# ESP-WROOM32-Breakout_v10.net
KiCad netlist of a schematic drawn in EAGLE
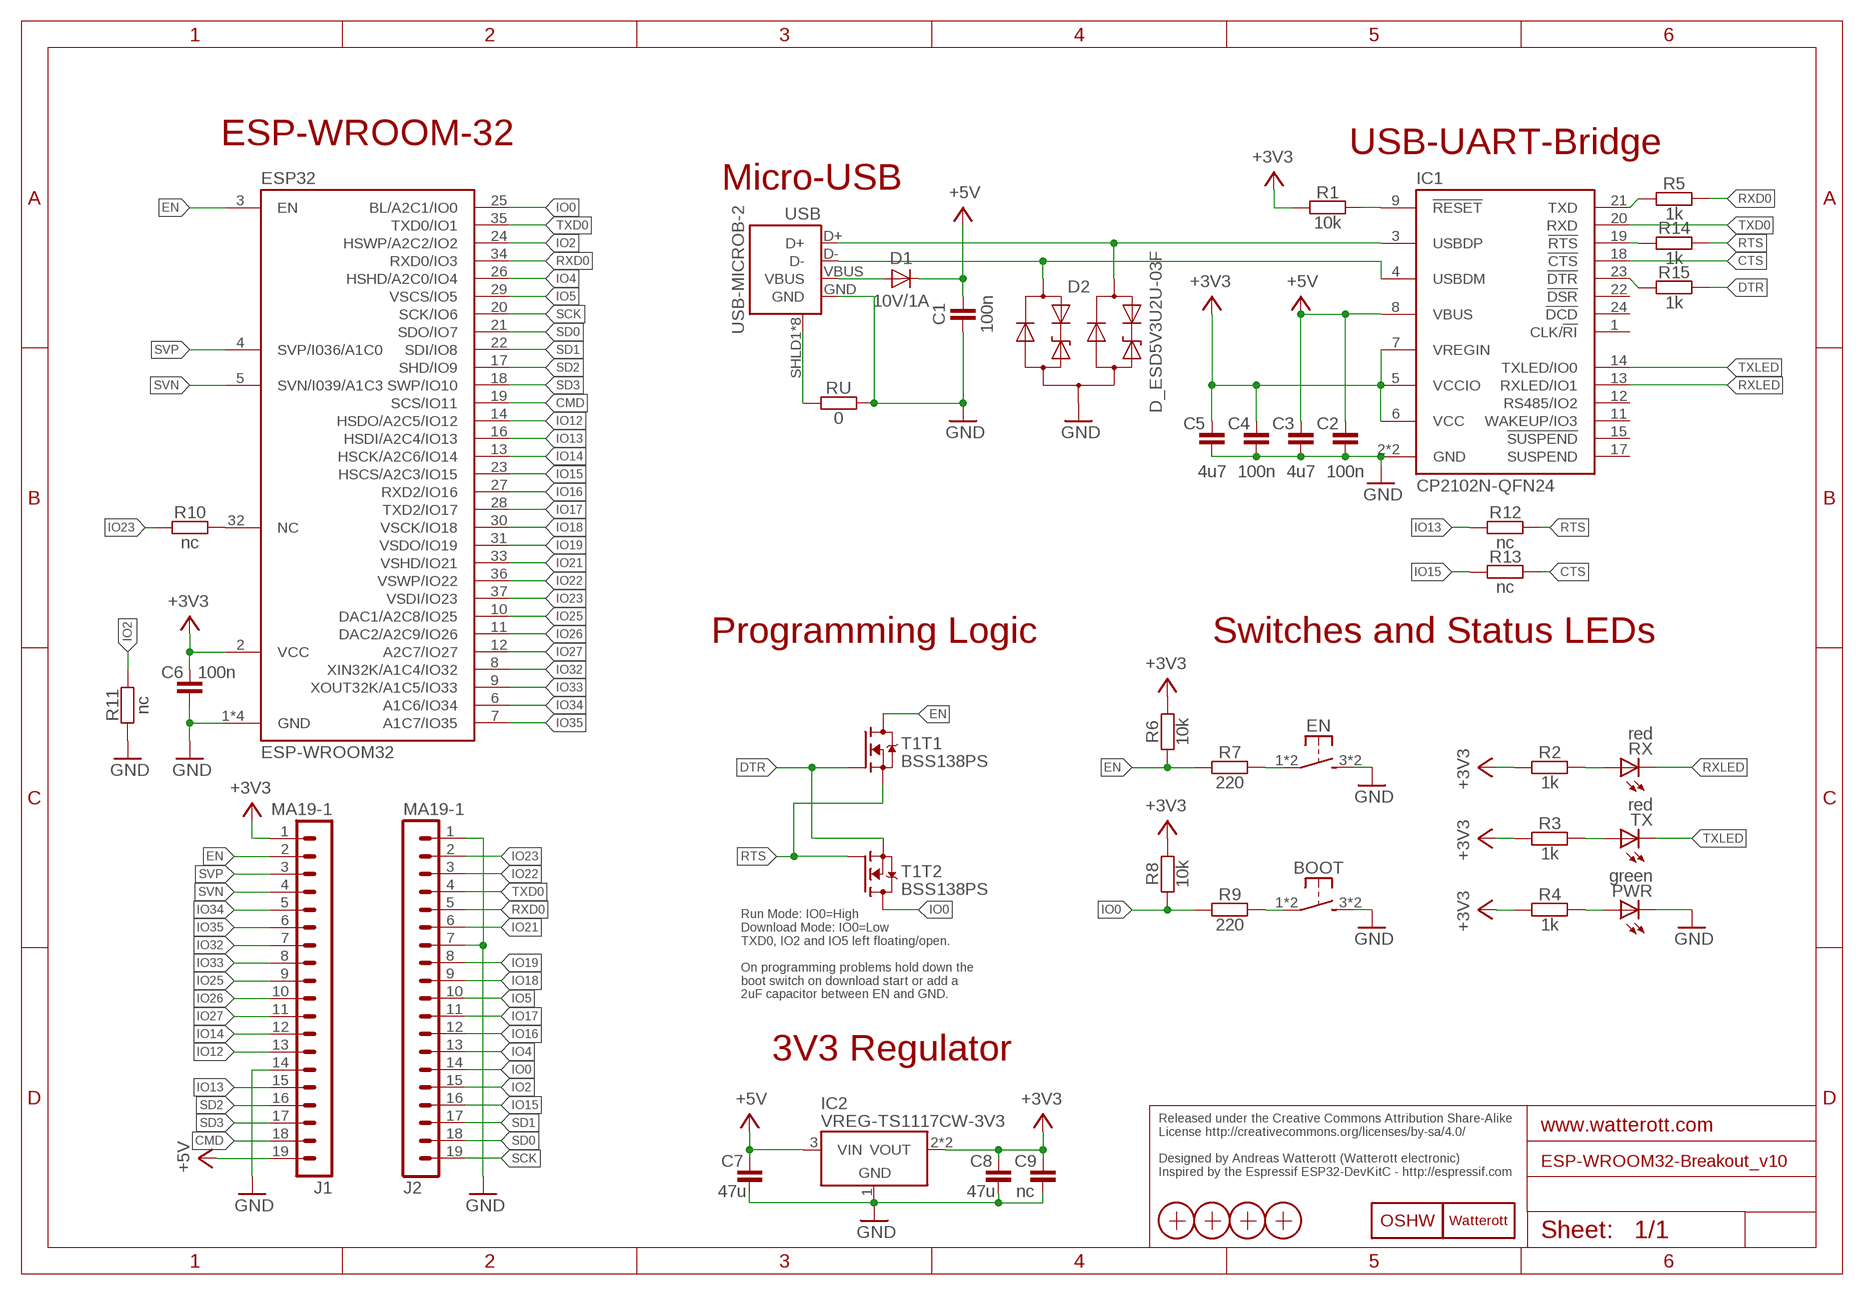
[diagram p0: schematic, sheet 1]

(export (version "E")
  (design (tool "Eeschema 10.0.6"))
  (components
    (comp (ref "BOOT")
      (value "SW-TACTILE-PTS840P")
      (footprint "eagle-import:PTS840P")
      (libsource (lib "eagle-import") (part "SW-TACTILE-PTS840P"))
    )
    (comp (ref "C1")
      (value "100n")
      (footprint "eagle-import:C0402")
      (libsource (lib "eagle-import") (part "CAPACITOR-0402"))
    )
    (comp (ref "C2")
      (value "100n")
      (footprint "eagle-import:C0402")
      (libsource (lib "eagle-import") (part "CAPACITOR-0402"))
    )
    (comp (ref "C3")
      (value "4u7")
      (footprint "eagle-import:C0603")
      (libsource (lib "eagle-import") (part "CAPACITOR-0603"))
    )
    (comp (ref "C4")
      (value "100n")
      (footprint "eagle-import:C0402")
      (libsource (lib "eagle-import") (part "CAPACITOR-0402"))
    )
    (comp (ref "C5")
      (value "4u7")
      (footprint "eagle-import:C0603")
      (libsource (lib "eagle-import") (part "CAPACITOR-0603"))
    )
    (comp (ref "C6")
      (value "100n")
      (footprint "eagle-import:C0402")
      (libsource (lib "eagle-import") (part "CAPACITOR-0402"))
    )
    (comp (ref "C7")
      (value "47u")
      (footprint "eagle-import:C1206")
      (libsource (lib "eagle-import") (part "CAPACITOR-1206"))
    )
    (comp (ref "C8")
      (value "47u")
      (footprint "eagle-import:C1206")
      (libsource (lib "eagle-import") (part "CAPACITOR-1206"))
    )
    (comp (ref "C9")
      (value "nc")
      (footprint "eagle-import:C1206")
      (libsource (lib "eagle-import") (part "CAPACITOR-1206"))
    )
    (comp (ref "D1")
      (value "10V/1A")
      (footprint "eagle-import:SMA_DO214AC")
      (libsource (lib "eagle-import") (part "DIODE-SMA"))
    )
    (comp (ref "D2")
      (value "D_ESD5V3U2U-03F")
      (footprint "eagle-import:SOT723")
      (libsource (lib "eagle-import") (part "D_ESD5V3U2U-03F"))
    )
    (comp (ref "EN")
      (value "SW-TACTILE-PTS840P")
      (footprint "eagle-import:PTS840P")
      (libsource (lib "eagle-import") (part "SW-TACTILE-PTS840P"))
    )
    (comp (ref "ESP32")
      (value "ESP-WROOM32")
      (footprint "eagle-import:ESP-WROOM32")
      (libsource (lib "eagle-import") (part "ESP-WROOM32"))
    )
    (comp (ref "IC1")
      (value "CP2102N-QFN24")
      (footprint "eagle-import:QFN24-PAD")
      (libsource (lib "eagle-import") (part "CP2102N-QFN24"))
    )
    (comp (ref "IC2")
      (value "VREG-TS1117CW-3V3")
      (footprint "eagle-import:SOT223")
      (libsource (lib "eagle-import") (part "VREG-TS1117CW-3V3"))
    )
    (comp (ref "J1")
      (value "MA19-1")
      (footprint "eagle-import:MA19-1")
      (libsource (lib "eagle-import") (part "MA19-1"))
    )
    (comp (ref "J2")
      (value "MA19-1")
      (footprint "eagle-import:MA19-1")
      (libsource (lib "eagle-import") (part "MA19-1"))
    )
    (comp (ref "LOGO2")
      (value "OSHW_LOGOX0070")
      (footprint "eagle-import:OSHW_6X70")
      (libsource (lib "eagle-import") (part "OSHW_LOGOX0070"))
    )
    (comp (ref "LOGO4")
      (value "LOGO-S_PLACE_M")
      (footprint "eagle-import:SPARK_TPLACE_M")
      (libsource (lib "eagle-import") (part "LOGO-S_PLACE_M"))
    )
    (comp (ref "PWR")
      (value "green")
      (footprint "eagle-import:C0603")
      (libsource (lib "eagle-import") (part "LED-0603"))
    )
    (comp (ref "R1")
      (value "10k")
      (footprint "eagle-import:C0402")
      (libsource (lib "eagle-import") (part "RESISTOR-0402"))
    )
    (comp (ref "R2")
      (value "1k")
      (footprint "eagle-import:C0402")
      (libsource (lib "eagle-import") (part "RESISTOR-0402"))
    )
    (comp (ref "R3")
      (value "1k")
      (footprint "eagle-import:C0402")
      (libsource (lib "eagle-import") (part "RESISTOR-0402"))
    )
    (comp (ref "R4")
      (value "1k")
      (footprint "eagle-import:C0402")
      (libsource (lib "eagle-import") (part "RESISTOR-0402"))
    )
    (comp (ref "R5")
      (value "1k")
      (footprint "eagle-import:C0402")
      (libsource (lib "eagle-import") (part "RESISTOR-0402"))
    )
    (comp (ref "R6")
      (value "10k")
      (footprint "eagle-import:C0402")
      (libsource (lib "eagle-import") (part "RESISTOR-0402"))
    )
    (comp (ref "R7")
      (value "220")
      (footprint "eagle-import:C0402")
      (libsource (lib "eagle-import") (part "RESISTOR-0402"))
    )
    (comp (ref "R8")
      (value "10k")
      (footprint "eagle-import:C0402")
      (libsource (lib "eagle-import") (part "RESISTOR-0402"))
    )
    (comp (ref "R9")
      (value "220")
      (footprint "eagle-import:C0402")
      (libsource (lib "eagle-import") (part "RESISTOR-0402"))
    )
    (comp (ref "R10")
      (value "nc")
      (footprint "eagle-import:C0402")
      (libsource (lib "eagle-import") (part "RESISTOR-0402"))
    )
    (comp (ref "R11")
      (value "nc")
      (footprint "eagle-import:C0402")
      (libsource (lib "eagle-import") (part "RESISTOR-0402"))
    )
    (comp (ref "R12")
      (value "nc")
      (footprint "eagle-import:C0402")
      (libsource (lib "eagle-import") (part "RESISTOR-0402"))
    )
    (comp (ref "R13")
      (value "nc")
      (footprint "eagle-import:C0402")
      (libsource (lib "eagle-import") (part "RESISTOR-0402"))
    )
    (comp (ref "R14")
      (value "1k")
      (footprint "eagle-import:C0402")
      (libsource (lib "eagle-import") (part "RESISTOR-0402"))
    )
    (comp (ref "R15")
      (value "1k")
      (footprint "eagle-import:C0402")
      (libsource (lib "eagle-import") (part "RESISTOR-0402"))
    )
    (comp (ref "RU")
      (value "0")
      (footprint "eagle-import:C0402")
      (libsource (lib "eagle-import") (part "RESISTOR-0402"))
    )
    (comp (ref "RX")
      (value "red")
      (footprint "eagle-import:C0603")
      (libsource (lib "eagle-import") (part "LED-0603"))
    )
    (comp (ref "T1")
      (value "BSS138PS")
      (footprint "eagle-import:SOT363")
      (libsource (lib "eagle-import") (part "BSS138PS"))
    )
    (comp (ref "TX")
      (value "red")
      (footprint "eagle-import:C0603")
      (libsource (lib "eagle-import") (part "LED-0603"))
    )
    (comp (ref "USB")
      (value "USB-MICROB-2")
      (footprint "eagle-import:USB-MICROB-10118194")
      (libsource (lib "eagle-import") (part "USB-MICROB-2"))
    )
    (comp (ref "X1")
      (value "PASSER-07")
      (footprint "eagle-import:PASSER_07MM")
      (libsource (lib "eagle-import") (part "PASSER-07"))
    )
    (comp (ref "X2")
      (value "PASSER-07")
      (footprint "eagle-import:PASSER_07MM")
      (libsource (lib "eagle-import") (part "PASSER-07"))
    )
    (comp (ref "X3")
      (value "PASSER-07")
      (footprint "eagle-import:PASSER_07MM")
      (libsource (lib "eagle-import") (part "PASSER-07"))
    )
    (comp (ref "X4")
      (value "PASSER-07")
      (footprint "eagle-import:PASSER_07MM")
      (libsource (lib "eagle-import") (part "PASSER-07"))
    )
  )
  (nets
    (net (code "1") (name "+3V3") (class "Default")
      (node (ref "C4") (pin "2") (pinfunction "2_2") (pintype "passive"))
      (node (ref "C5") (pin "2") (pinfunction "2_2") (pintype "passive"))
      (node (ref "C6") (pin "2") (pinfunction "2_2") (pintype "passive"))
      (node (ref "C8") (pin "2") (pinfunction "2_2") (pintype "passive"))
      (node (ref "C9") (pin "2") (pinfunction "2_2") (pintype "passive"))
      (node (ref "ESP32") (pin "2") (pinfunction "VCC_2") (pintype "power_in"))
      (node (ref "IC1") (pin "5") (pinfunction "VCCIO_5") (pintype "power_in"))
      (node (ref "IC1") (pin "6") (pinfunction "VCC_6") (pintype "power_in"))
      (node (ref "IC1") (pin "7") (pinfunction "VREGIN_7") (pintype "power_in"))
      (node (ref "IC2") (pin "2") (pinfunction "VOUT_2") (pintype "power_in"))
      (node (ref "IC2") (pin "4") (pinfunction "VOUT_4") (pintype "power_in"))
      (node (ref "J1") (pin "1") (pinfunction "1_1") (pintype "passive"))
      (node (ref "R1") (pin "1") (pinfunction "1_1") (pintype "passive"))
      (node (ref "R2") (pin "1") (pinfunction "1_1") (pintype "passive"))
      (node (ref "R3") (pin "1") (pinfunction "1_1") (pintype "passive"))
      (node (ref "R4") (pin "1") (pinfunction "1_1") (pintype "passive"))
      (node (ref "R6") (pin "2") (pinfunction "2_2") (pintype "passive"))
      (node (ref "R8") (pin "2") (pinfunction "2_2") (pintype "passive"))
    )
    (net (code "2") (name "+5V") (class "Default")
      (node (ref "C1") (pin "2") (pinfunction "2_2") (pintype "passive"))
      (node (ref "C2") (pin "2") (pinfunction "2_2") (pintype "passive"))
      (node (ref "C3") (pin "2") (pinfunction "2_2") (pintype "passive"))
      (node (ref "C7") (pin "2") (pinfunction "2_2") (pintype "passive"))
      (node (ref "D1") (pin "C") (pinfunction "C_C") (pintype "passive"))
      (node (ref "IC1") (pin "8") (pinfunction "VBUS_8") (pintype "power_in"))
      (node (ref "IC2") (pin "3") (pinfunction "VIN_3") (pintype "power_in"))
      (node (ref "J1") (pin "19") (pinfunction "19_19") (pintype "passive"))
    )
    (net (code "3") (name "CMD") (class "Default")
      (node (ref "ESP32") (pin "19") (pinfunction "SCS/IO11_19") (pintype "bidirectional"))
      (node (ref "J1") (pin "18") (pinfunction "18_18") (pintype "passive"))
    )
    (net (code "4") (name "CTS") (class "Default")
      (node (ref "IC1") (pin "18") (pinfunction "~{CTS}_18") (pintype "bidirectional"))
      (node (ref "R13") (pin "2") (pinfunction "2_2") (pintype "passive"))
    )
    (net (code "5") (name "DTR") (class "Default")
      (node (ref "R15") (pin "2") (pinfunction "2_2") (pintype "passive"))
      (node (ref "T1") (pin "2") (pinfunction "G_2") (pintype "passive"))
      (node (ref "T1") (pin "4") (pinfunction "S_4") (pintype "passive"))
    )
    (net (code "6") (name "EN") (class "Default")
      (node (ref "ESP32") (pin "3") (pinfunction "EN_3") (pintype "bidirectional"))
      (node (ref "J1") (pin "2") (pinfunction "2_2") (pintype "passive"))
      (node (ref "R6") (pin "1") (pinfunction "1_1") (pintype "passive"))
      (node (ref "R7") (pin "1") (pinfunction "1_1") (pintype "passive"))
      (node (ref "T1") (pin "6") (pinfunction "D_6") (pintype "passive"))
    )
    (net (code "7") (name "GND") (class "Default")
      (node (ref "BOOT") (pin "3") (pinfunction "S1_3") (pintype "passive"))
      (node (ref "BOOT") (pin "4") (pinfunction "S1_4") (pintype "passive"))
      (node (ref "C1") (pin "1") (pinfunction "1_1") (pintype "passive"))
      (node (ref "C2") (pin "1") (pinfunction "1_1") (pintype "passive"))
      (node (ref "C3") (pin "1") (pinfunction "1_1") (pintype "passive"))
      (node (ref "C4") (pin "1") (pinfunction "1_1") (pintype "passive"))
      (node (ref "C5") (pin "1") (pinfunction "1_1") (pintype "passive"))
      (node (ref "C6") (pin "1") (pinfunction "1_1") (pintype "passive"))
      (node (ref "C7") (pin "1") (pinfunction "1_1") (pintype "passive"))
      (node (ref "C8") (pin "1") (pinfunction "1_1") (pintype "passive"))
      (node (ref "C9") (pin "1") (pinfunction "1_1") (pintype "passive"))
      (node (ref "D2") (pin "3") (pinfunction "A_3") (pintype "passive"))
      (node (ref "EN") (pin "3") (pinfunction "S1_3") (pintype "passive"))
      (node (ref "EN") (pin "4") (pinfunction "S1_4") (pintype "passive"))
      (node (ref "ESP32") (pin "1") (pinfunction "GND_1") (pintype "power_in"))
      (node (ref "ESP32") (pin "15") (pinfunction "GND_15") (pintype "power_in"))
      (node (ref "ESP32") (pin "38") (pinfunction "GND_38") (pintype "power_in"))
      (node (ref "ESP32") (pin "TP") (pinfunction "GND_TP") (pintype "power_in"))
      (node (ref "IC1") (pin "2") (pinfunction "GND_2") (pintype "power_in"))
      (node (ref "IC1") (pin "TP") (pinfunction "GND_TP") (pintype "power_in"))
      (node (ref "IC2") (pin "1") (pinfunction "GND_1") (pintype "power_in"))
      (node (ref "J1") (pin "14") (pinfunction "14_14") (pintype "passive"))
      (node (ref "J2") (pin "1") (pinfunction "1_1") (pintype "passive"))
      (node (ref "J2") (pin "7") (pinfunction "7_7") (pintype "passive"))
      (node (ref "PWR") (pin "C") (pinfunction "C_C") (pintype "passive"))
      (node (ref "R11") (pin "1") (pinfunction "1_1") (pintype "passive"))
      (node (ref "RU") (pin "2") (pinfunction "2_2") (pintype "passive"))
      (node (ref "USB") (pin "GND") (pinfunction "GND_GND") (pintype "power_in"))
    )
    (net (code "8") (name "IO0") (class "Default")
      (node (ref "ESP32") (pin "25") (pinfunction "BL/A2C1/IO0_25") (pintype "bidirectional"))
      (node (ref "J2") (pin "14") (pinfunction "14_14") (pintype "passive"))
      (node (ref "R8") (pin "1") (pinfunction "1_1") (pintype "passive"))
      (node (ref "R9") (pin "1") (pinfunction "1_1") (pintype "passive"))
      (node (ref "T1") (pin "3") (pinfunction "D_3") (pintype "passive"))
    )
    (net (code "9") (name "IO2") (class "Default")
      (node (ref "ESP32") (pin "24") (pinfunction "HSWP/A2C2/IO2_24") (pintype "bidirectional"))
      (node (ref "J2") (pin "15") (pinfunction "15_15") (pintype "passive"))
      (node (ref "R11") (pin "2") (pinfunction "2_2") (pintype "passive"))
    )
    (net (code "10") (name "IO4") (class "Default")
      (node (ref "ESP32") (pin "26") (pinfunction "HSHD/A2C0/IO4_26") (pintype "bidirectional"))
      (node (ref "J2") (pin "13") (pinfunction "13_13") (pintype "passive"))
    )
    (net (code "11") (name "IO5") (class "Default")
      (node (ref "ESP32") (pin "29") (pinfunction "VSCS/IO5_29") (pintype "bidirectional"))
      (node (ref "J2") (pin "10") (pinfunction "10_10") (pintype "passive"))
    )
    (net (code "12") (name "IO12") (class "Default")
      (node (ref "ESP32") (pin "14") (pinfunction "HSDO/A2C5/IO12_14") (pintype "bidirectional"))
      (node (ref "J1") (pin "13") (pinfunction "13_13") (pintype "passive"))
    )
    (net (code "13") (name "IO13") (class "Default")
      (node (ref "ESP32") (pin "16") (pinfunction "HSDI/A2C4/IO13_16") (pintype "bidirectional"))
      (node (ref "J1") (pin "15") (pinfunction "15_15") (pintype "passive"))
      (node (ref "R12") (pin "1") (pinfunction "1_1") (pintype "passive"))
    )
    (net (code "14") (name "IO14") (class "Default")
      (node (ref "ESP32") (pin "13") (pinfunction "HSCK/A2C6/IO14_13") (pintype "bidirectional"))
      (node (ref "J1") (pin "12") (pinfunction "12_12") (pintype "passive"))
    )
    (net (code "15") (name "IO15") (class "Default")
      (node (ref "ESP32") (pin "23") (pinfunction "HSCS/A2C3/IO15_23") (pintype "bidirectional"))
      (node (ref "J2") (pin "16") (pinfunction "16_16") (pintype "passive"))
      (node (ref "R13") (pin "1") (pinfunction "1_1") (pintype "passive"))
    )
    (net (code "16") (name "IO16") (class "Default")
      (node (ref "ESP32") (pin "27") (pinfunction "RXD2/IO16_27") (pintype "bidirectional"))
      (node (ref "J2") (pin "12") (pinfunction "12_12") (pintype "passive"))
    )
    (net (code "17") (name "IO17") (class "Default")
      (node (ref "ESP32") (pin "28") (pinfunction "TXD2/IO17_28") (pintype "bidirectional"))
      (node (ref "J2") (pin "11") (pinfunction "11_11") (pintype "passive"))
    )
    (net (code "18") (name "IO18") (class "Default")
      (node (ref "ESP32") (pin "30") (pinfunction "VSCK/IO18_30") (pintype "bidirectional"))
      (node (ref "J2") (pin "9") (pinfunction "9_9") (pintype "passive"))
    )
    (net (code "19") (name "IO19") (class "Default")
      (node (ref "ESP32") (pin "31") (pinfunction "VSDO/IO19_31") (pintype "bidirectional"))
      (node (ref "J2") (pin "8") (pinfunction "8_8") (pintype "passive"))
    )
    (net (code "20") (name "IO21") (class "Default")
      (node (ref "ESP32") (pin "33") (pinfunction "VSHD/IO21_33") (pintype "bidirectional"))
      (node (ref "J2") (pin "6") (pinfunction "6_6") (pintype "passive"))
    )
    (net (code "21") (name "IO22") (class "Default")
      (node (ref "ESP32") (pin "36") (pinfunction "VSWP/IO22_36") (pintype "bidirectional"))
      (node (ref "J2") (pin "3") (pinfunction "3_3") (pintype "passive"))
    )
    (net (code "22") (name "IO23") (class "Default")
      (node (ref "ESP32") (pin "37") (pinfunction "VSDI/IO23_37") (pintype "bidirectional"))
      (node (ref "J2") (pin "2") (pinfunction "2_2") (pintype "passive"))
      (node (ref "R10") (pin "1") (pinfunction "1_1") (pintype "passive"))
    )
    (net (code "23") (name "IO25") (class "Default")
      (node (ref "ESP32") (pin "10") (pinfunction "DAC1/A2C8/IO25_10") (pintype "bidirectional"))
      (node (ref "J1") (pin "9") (pinfunction "9_9") (pintype "passive"))
    )
    (net (code "24") (name "IO26") (class "Default")
      (node (ref "ESP32") (pin "11") (pinfunction "DAC2/A2C9/IO26_11") (pintype "bidirectional"))
      (node (ref "J1") (pin "10") (pinfunction "10_10") (pintype "passive"))
    )
    (net (code "25") (name "IO27") (class "Default")
      (node (ref "ESP32") (pin "12") (pinfunction "A2C7/IO27_12") (pintype "bidirectional"))
      (node (ref "J1") (pin "11") (pinfunction "11_11") (pintype "passive"))
    )
    (net (code "26") (name "IO32") (class "Default")
      (node (ref "ESP32") (pin "8") (pinfunction "XIN32K/A1C4/IO32_8") (pintype "bidirectional"))
      (node (ref "J1") (pin "7") (pinfunction "7_7") (pintype "passive"))
    )
    (net (code "27") (name "IO33") (class "Default")
      (node (ref "ESP32") (pin "9") (pinfunction "XOUT32K/A1C5/IO33_9") (pintype "bidirectional"))
      (node (ref "J1") (pin "8") (pinfunction "8_8") (pintype "passive"))
    )
    (net (code "28") (name "IO34") (class "Default")
      (node (ref "ESP32") (pin "6") (pinfunction "A1C6/IO34_6") (pintype "bidirectional"))
      (node (ref "J1") (pin "5") (pinfunction "5_5") (pintype "passive"))
    )
    (net (code "29") (name "IO35") (class "Default")
      (node (ref "ESP32") (pin "7") (pinfunction "A1C7/IO35_7") (pintype "bidirectional"))
      (node (ref "J1") (pin "6") (pinfunction "6_6") (pintype "passive"))
    )
    (net (code "30") (name "Net-(BOOT-P1-Pad1)") (class "Default")
      (node (ref "BOOT") (pin "1") (pinfunction "P1_1") (pintype "passive"))
      (node (ref "BOOT") (pin "2") (pinfunction "P1_2") (pintype "passive"))
      (node (ref "R9") (pin "2") (pinfunction "2_2") (pintype "passive"))
    )
    (net (code "31") (name "Net-(D1-PadA)") (class "Default")
      (node (ref "D1") (pin "A") (pinfunction "A_A") (pintype "passive"))
      (node (ref "USB") (pin "VBUS") (pinfunction "VBUS_VBUS") (pintype "power_in"))
    )
    (net (code "32") (name "Net-(D2-C1)") (class "Default")
      (node (ref "D2") (pin "1") (pinfunction "C1_1") (pintype "passive"))
      (node (ref "IC1") (pin "4") (pinfunction "USBDM_4") (pintype "bidirectional"))
      (node (ref "USB") (pin "D-") (pinfunction "D-_D-") (pintype "bidirectional"))
    )
    (net (code "33") (name "Net-(D2-C2)") (class "Default")
      (node (ref "D2") (pin "2") (pinfunction "C2_2") (pintype "passive"))
      (node (ref "IC1") (pin "3") (pinfunction "USBDP_3") (pintype "bidirectional"))
      (node (ref "USB") (pin "D+") (pinfunction "D+_D+") (pintype "bidirectional"))
    )
    (net (code "34") (name "Net-(EN-P1-Pad1)") (class "Default")
      (node (ref "EN") (pin "1") (pinfunction "P1_1") (pintype "passive"))
      (node (ref "EN") (pin "2") (pinfunction "P1_2") (pintype "passive"))
      (node (ref "R7") (pin "2") (pinfunction "2_2") (pintype "passive"))
    )
    (net (code "35") (name "Net-(ESP32-NC)") (class "Default")
      (node (ref "ESP32") (pin "32") (pinfunction "NC_32") (pintype "bidirectional"))
      (node (ref "R10") (pin "2") (pinfunction "2_2") (pintype "passive"))
    )
    (net (code "36") (name "Net-(IC1-TXD)") (class "Default")
      (node (ref "IC1") (pin "21") (pinfunction "TXD_21") (pintype "bidirectional"))
      (node (ref "R5") (pin "1") (pinfunction "1_1") (pintype "passive"))
    )
    (net (code "37") (name "Net-(IC1-~{DTR})") (class "Default")
      (node (ref "IC1") (pin "23") (pinfunction "~{DTR}_23") (pintype "bidirectional"))
      (node (ref "R15") (pin "1") (pinfunction "1_1") (pintype "passive"))
    )
    (net (code "38") (name "Net-(IC1-~{RESET})") (class "Default")
      (node (ref "IC1") (pin "9") (pinfunction "~{RESET}_9") (pintype "bidirectional"))
      (node (ref "R1") (pin "2") (pinfunction "2_2") (pintype "passive"))
    )
    (net (code "39") (name "Net-(IC1-~{RTS})") (class "Default")
      (node (ref "IC1") (pin "19") (pinfunction "~{RTS}_19") (pintype "bidirectional"))
      (node (ref "R14") (pin "1") (pinfunction "1_1") (pintype "passive"))
    )
    (net (code "40") (name "Net-(PWR-PadA)") (class "Default")
      (node (ref "PWR") (pin "A") (pinfunction "A_A") (pintype "passive"))
      (node (ref "R4") (pin "2") (pinfunction "2_2") (pintype "passive"))
    )
    (net (code "41") (name "Net-(R2-Pad2)") (class "Default")
      (node (ref "R2") (pin "2") (pinfunction "2_2") (pintype "passive"))
      (node (ref "RX") (pin "A") (pinfunction "A_A") (pintype "passive"))
    )
    (net (code "42") (name "Net-(R3-Pad2)") (class "Default")
      (node (ref "R3") (pin "2") (pinfunction "2_2") (pintype "passive"))
      (node (ref "TX") (pin "A") (pinfunction "A_A") (pintype "passive"))
    )
    (net (code "43") (name "Net-(RU-Pad1)") (class "Default")
      (node (ref "RU") (pin "1") (pinfunction "1_1") (pintype "passive"))
      (node (ref "USB") (pin "SHLD1") (pinfunction "SHIELD_SHLD1") (pintype "passive"))
      (node (ref "USB") (pin "SHLD2") (pinfunction "SHIELD_SHLD2") (pintype "passive"))
      (node (ref "USB") (pin "SHLD3") (pinfunction "SHIELD_SHLD3") (pintype "passive"))
      (node (ref "USB") (pin "SHLD4") (pinfunction "SHIELD_SHLD4") (pintype "passive"))
      (node (ref "USB") (pin "SHLD5") (pinfunction "SHIELD_SHLD5") (pintype "passive"))
      (node (ref "USB") (pin "SHLD6") (pinfunction "SHIELD_SHLD6") (pintype "passive"))
      (node (ref "USB") (pin "SHLD7") (pinfunction "SHIELD_SHLD7") (pintype "passive"))
      (node (ref "USB") (pin "SHLD8") (pinfunction "SHIELD_SHLD8") (pintype "passive"))
    )
    (net (code "44") (name "RTS") (class "Default")
      (node (ref "R12") (pin "2") (pinfunction "2_2") (pintype "passive"))
      (node (ref "R14") (pin "2") (pinfunction "2_2") (pintype "passive"))
      (node (ref "T1") (pin "1") (pinfunction "S_1") (pintype "passive"))
      (node (ref "T1") (pin "5") (pinfunction "G_5") (pintype "passive"))
    )
    (net (code "45") (name "RXD0") (class "Default")
      (node (ref "ESP32") (pin "34") (pinfunction "RXD0/IO3_34") (pintype "bidirectional"))
      (node (ref "J2") (pin "5") (pinfunction "5_5") (pintype "passive"))
      (node (ref "R5") (pin "2") (pinfunction "2_2") (pintype "passive"))
    )
    (net (code "46") (name "RXLED") (class "Default")
      (node (ref "IC1") (pin "13") (pinfunction "RXLED/IO1_13") (pintype "bidirectional"))
      (node (ref "RX") (pin "C") (pinfunction "C_C") (pintype "passive"))
    )
    (net (code "47") (name "SCK") (class "Default")
      (node (ref "ESP32") (pin "20") (pinfunction "SCK/IO6_20") (pintype "bidirectional"))
      (node (ref "J2") (pin "19") (pinfunction "19_19") (pintype "passive"))
    )
    (net (code "48") (name "SD0") (class "Default")
      (node (ref "ESP32") (pin "21") (pinfunction "SDO/IO7_21") (pintype "bidirectional"))
      (node (ref "J2") (pin "18") (pinfunction "18_18") (pintype "passive"))
    )
    (net (code "49") (name "SD1") (class "Default")
      (node (ref "ESP32") (pin "22") (pinfunction "SDI/IO8_22") (pintype "bidirectional"))
      (node (ref "J2") (pin "17") (pinfunction "17_17") (pintype "passive"))
    )
    (net (code "50") (name "SD2") (class "Default")
      (node (ref "ESP32") (pin "17") (pinfunction "SHD/IO9_17") (pintype "bidirectional"))
      (node (ref "J1") (pin "16") (pinfunction "16_16") (pintype "passive"))
    )
    (net (code "51") (name "SD3") (class "Default")
      (node (ref "ESP32") (pin "18") (pinfunction "SWP/IO10_18") (pintype "bidirectional"))
      (node (ref "J1") (pin "17") (pinfunction "17_17") (pintype "passive"))
    )
    (net (code "52") (name "SVN") (class "Default")
      (node (ref "ESP32") (pin "5") (pinfunction "SVN/I039/A1C3_5") (pintype "bidirectional"))
      (node (ref "J1") (pin "4") (pinfunction "4_4") (pintype "passive"))
    )
    (net (code "53") (name "SVP") (class "Default")
      (node (ref "ESP32") (pin "4") (pinfunction "SVP/I036/A1C0_4") (pintype "bidirectional"))
      (node (ref "J1") (pin "3") (pinfunction "3_3") (pintype "passive"))
    )
    (net (code "54") (name "TXD0") (class "Default")
      (node (ref "ESP32") (pin "35") (pinfunction "TXD0/IO1_35") (pintype "bidirectional"))
      (node (ref "IC1") (pin "20") (pinfunction "RXD_20") (pintype "bidirectional"))
      (node (ref "J2") (pin "4") (pinfunction "4_4") (pintype "passive"))
    )
    (net (code "55") (name "TXLED") (class "Default")
      (node (ref "IC1") (pin "14") (pinfunction "TXLED/IO0_14") (pintype "bidirectional"))
      (node (ref "TX") (pin "C") (pinfunction "C_C") (pintype "passive"))
    )
    (net (code "56") (name "unconnected-(IC1-CLK{slash}~{RI}-Pad1)") (class "Default")
      (node (ref "IC1") (pin "1") (pinfunction "CLK/~{RI}_1") (pintype "bidirectional"))
    )
    (net (code "57") (name "unconnected-(IC1-RS485{slash}IO2-Pad12)") (class "Default")
      (node (ref "IC1") (pin "12") (pinfunction "RS485/IO2_12") (pintype "bidirectional"))
    )
    (net (code "58") (name "unconnected-(IC1-SUSPEND-Pad17)") (class "Default")
      (node (ref "IC1") (pin "17") (pinfunction "SUSPEND_17") (pintype "bidirectional"))
    )
    (net (code "59") (name "unconnected-(IC1-WAKEUP{slash}IO3-Pad11)") (class "Default")
      (node (ref "IC1") (pin "11") (pinfunction "WAKEUP/IO3_11") (pintype "bidirectional"))
    )
    (net (code "60") (name "unconnected-(IC1-~{DCD}-Pad24)") (class "Default")
      (node (ref "IC1") (pin "24") (pinfunction "~{DCD}_24") (pintype "bidirectional"))
    )
    (net (code "61") (name "unconnected-(IC1-~{DSR}-Pad22)") (class "Default")
      (node (ref "IC1") (pin "22") (pinfunction "~{DSR}_22") (pintype "bidirectional"))
    )
    (net (code "62") (name "unconnected-(IC1-~{SUSPEND}-Pad15)") (class "Default")
      (node (ref "IC1") (pin "15") (pinfunction "~{SUSPEND}_15") (pintype "bidirectional"))
    )
  )
)
